# coderbot_v5_0_rev_2.net
KiCad netlist of a schematic drawn in EAGLE
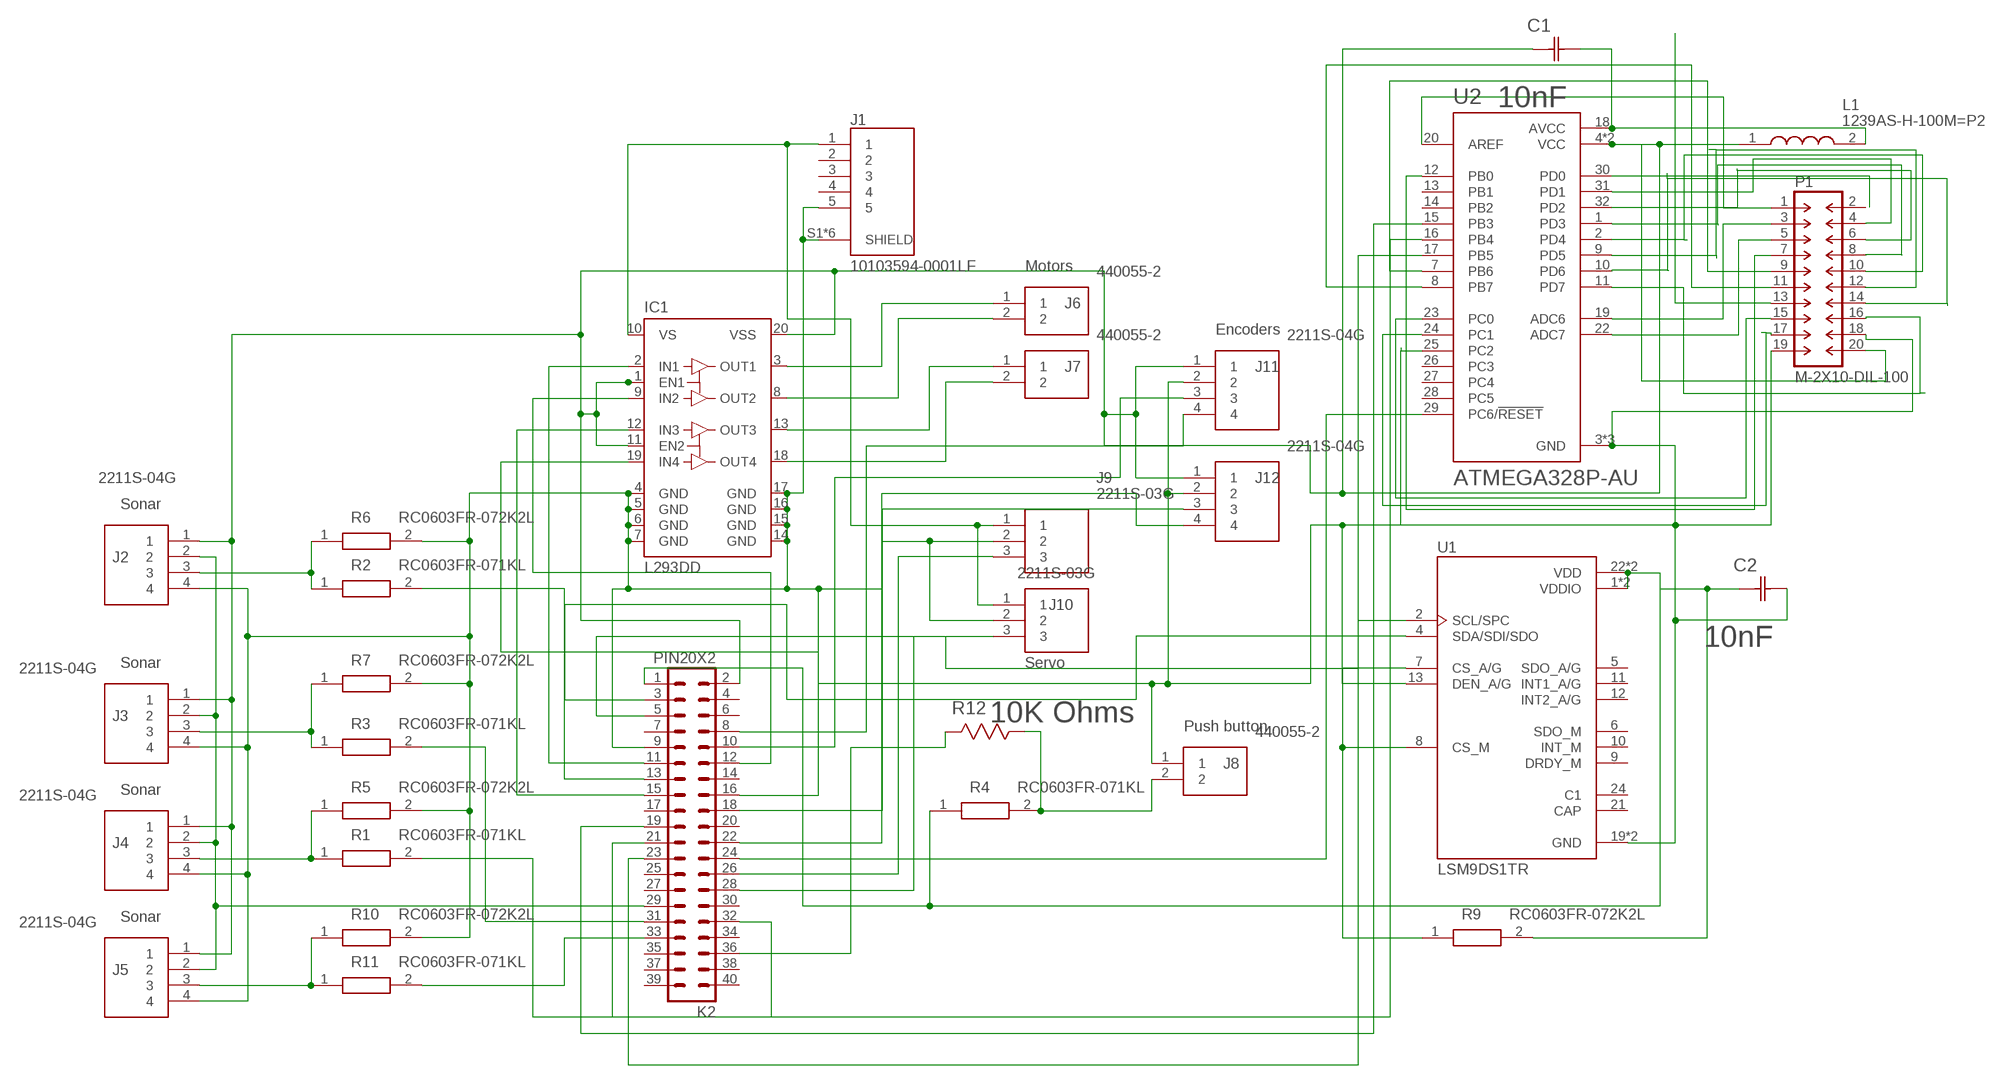
[diagram p0: schematic, sheet 1]

(export (version "E")
  (design (tool "Eeschema 10.0.6"))
  (components
    (comp (ref "C1")
      (value "10nF")
      (footprint "eagle-import:CAPC1005X55N")
      (fields (field (name "MPN") "CC0402KRX7R7BB103") (field (name "TOLERANCE") "±10%"))
      (libsource (lib "eagle-import") (part "CC0402KRX7R7BB103"))
    )
    (comp (ref "C2")
      (value "10nF")
      (footprint "eagle-import:CAPC1005X55N")
      (fields (field (name "MPN") "CC0402KRX7R7BB103") (field (name "TOLERANCE") "±10%"))
      (libsource (lib "eagle-import") (part "CC0402KRX7R7BB103"))
    )
    (comp (ref "IC1")
      (value "L293DD")
      (footprint "eagle-import:SO20")
      (libsource (lib "eagle-import") (part "L293DD"))
    )
    (comp (ref "J1")
      (value "10103594-0001LF")
      (footprint "eagle-import:FCI_10103594-0001LF")
      (fields (field (name "DIGI-KEY_PART_NUMBER") "609-4050-1-ND") (field (name "MF") "Amphenol ICC"))
      (libsource (lib "eagle-import") (part "10103594-0001LF"))
    )
    (comp (ref "J2")
      (value "2211S-04G")
      (footprint "eagle-import:HDRV4W90P0X254_1X4_1016X254X87")
      (libsource (lib "eagle-import") (part "2211S-04G"))
    )
    (comp (ref "J3")
      (value "2211S-04G")
      (footprint "eagle-import:HDRV4W90P0X254_1X4_1016X254X87")
      (libsource (lib "eagle-import") (part "2211S-04G"))
    )
    (comp (ref "J4")
      (value "2211S-04G")
      (footprint "eagle-import:HDRV4W90P0X254_1X4_1016X254X87")
      (libsource (lib "eagle-import") (part "2211S-04G"))
    )
    (comp (ref "J5")
      (value "2211S-04G")
      (footprint "eagle-import:HDRV4W90P0X254_1X4_1016X254X87")
      (libsource (lib "eagle-import") (part "2211S-04G"))
    )
    (comp (ref "J6")
      (value "440055-2")
      (footprint "eagle-import:SHDR2W70P0X200_1X2_600X770X525")
      (fields (field (name "MOUSER_PART_NUMBER") "571-440055-2"))
      (libsource (lib "eagle-import") (part "440055-2"))
    )
    (comp (ref "J7")
      (value "440055-2")
      (footprint "eagle-import:SHDR2W70P0X200_1X2_600X770X525")
      (fields (field (name "MOUSER_PART_NUMBER") "571-440055-2"))
      (libsource (lib "eagle-import") (part "440055-2"))
    )
    (comp (ref "J8")
      (value "440055-2")
      (footprint "eagle-import:SHDR2W70P0X200_1X2_600X770X525")
      (fields (field (name "MOUSER_PART_NUMBER") "571-440055-2"))
      (libsource (lib "eagle-import") (part "440055-2"))
    )
    (comp (ref "J9")
      (value "2211S-03G")
      (footprint "eagle-import:HDRV3W90P0X254_1X3_762X254X874")
      (libsource (lib "eagle-import") (part "2211S-03G"))
    )
    (comp (ref "J10")
      (value "2211S-03G")
      (footprint "eagle-import:HDRV3W90P0X254_1X3_762X254X874")
      (libsource (lib "eagle-import") (part "2211S-03G"))
    )
    (comp (ref "J11")
      (value "2211S-04G")
      (footprint "eagle-import:HDRV4W90P0X254_1X4_1016X254X87")
      (libsource (lib "eagle-import") (part "2211S-04G"))
    )
    (comp (ref "J12")
      (value "2211S-04G")
      (footprint "eagle-import:HDRV4W90P0X254_1X4_1016X254X87")
      (libsource (lib "eagle-import") (part "2211S-04G"))
    )
    (comp (ref "K2")
      (value "PIN20X2")
      (footprint "eagle-import:PIN_20X2")
      (libsource (lib "eagle-import") (part "PIN20X2"))
    )
    (comp (ref "L1")
      (value "1239AS-H-100M=P2")
      (footprint "eagle-import:INDC2520X120N")
      (fields
        (field (name "MOUSER_PART_NUMBER") "81-1239AS-H-100MP2")
        (field (name "RS_PART_NUMBER") "1453485")
      )
      (libsource (lib "eagle-import") (part "1239AS-H-100M=P2"))
    )
    (comp (ref "P1")
      (value "M-2X10-DIL-100")
      (footprint "eagle-import:DIL-100-2X10")
      (libsource (lib "eagle-import") (part "M-2X10-DIL-100"))
    )
    (comp (ref "R1")
      (value "RC0603FR-071KL")
      (footprint "eagle-import:RESC1608X55N")
      (fields
        (field (name "MOUSER_PART_NUMBER") "603-RC0603FR-071KL")
        (field (name "RS_PART_NUMBER") "5048928")
      )
      (libsource (lib "eagle-import") (part "RC0603FR-071KL"))
    )
    (comp (ref "R2")
      (value "RC0603FR-071KL")
      (footprint "eagle-import:RESC1608X55N")
      (fields
        (field (name "MOUSER_PART_NUMBER") "603-RC0603FR-071KL")
        (field (name "RS_PART_NUMBER") "5048928")
      )
      (libsource (lib "eagle-import") (part "RC0603FR-071KL"))
    )
    (comp (ref "R3")
      (value "RC0603FR-071KL")
      (footprint "eagle-import:RESC1608X55N")
      (fields
        (field (name "MOUSER_PART_NUMBER") "603-RC0603FR-071KL")
        (field (name "RS_PART_NUMBER") "5048928")
      )
      (libsource (lib "eagle-import") (part "RC0603FR-071KL"))
    )
    (comp (ref "R4")
      (value "RC0603FR-071KL")
      (footprint "eagle-import:RESC1608X55N")
      (fields
        (field (name "MOUSER_PART_NUMBER") "603-RC0603FR-071KL")
        (field (name "RS_PART_NUMBER") "5048928")
      )
      (libsource (lib "eagle-import") (part "RC0603FR-071KL"))
    )
    (comp (ref "R5")
      (value "RC0603FR-072K2L")
      (footprint "eagle-import:RESC1608X55N")
      (fields
        (field (name "MOUSER_PART_NUMBER") "603-RC0603FR-072K2L")
        (field (name "RS_PART_NUMBER") "5050319")
      )
      (libsource (lib "eagle-import") (part "RC0603FR-072K2L"))
    )
    (comp (ref "R6")
      (value "RC0603FR-072K2L")
      (footprint "eagle-import:RESC1608X55N")
      (fields
        (field (name "MOUSER_PART_NUMBER") "603-RC0603FR-072K2L")
        (field (name "RS_PART_NUMBER") "5050319")
      )
      (libsource (lib "eagle-import") (part "RC0603FR-072K2L"))
    )
    (comp (ref "R7")
      (value "RC0603FR-072K2L")
      (footprint "eagle-import:RESC1608X55N")
      (fields
        (field (name "MOUSER_PART_NUMBER") "603-RC0603FR-072K2L")
        (field (name "RS_PART_NUMBER") "5050319")
      )
      (libsource (lib "eagle-import") (part "RC0603FR-072K2L"))
    )
    (comp (ref "R9")
      (value "RC0603FR-072K2L")
      (footprint "eagle-import:RESC1608X55N")
      (fields
        (field (name "MOUSER_PART_NUMBER") "603-RC0603FR-072K2L")
        (field (name "RS_PART_NUMBER") "5050319")
      )
      (libsource (lib "eagle-import") (part "RC0603FR-072K2L"))
    )
    (comp (ref "R10")
      (value "RC0603FR-072K2L")
      (footprint "eagle-import:RESC1608X55N")
      (fields
        (field (name "MOUSER_PART_NUMBER") "603-RC0603FR-072K2L")
        (field (name "RS_PART_NUMBER") "5050319")
      )
      (libsource (lib "eagle-import") (part "RC0603FR-072K2L"))
    )
    (comp (ref "R11")
      (value "RC0603FR-071KL")
      (footprint "eagle-import:RESC1608X55N")
      (fields
        (field (name "MOUSER_PART_NUMBER") "603-RC0603FR-071KL")
        (field (name "RS_PART_NUMBER") "5048928")
      )
      (libsource (lib "eagle-import") (part "RC0603FR-071KL"))
    )
    (comp (ref "R12")
      (value "10K Ohms")
      (footprint "eagle-import:RESC1608X60N")
      (fields (field (name "MPN") "RC0603FR-0710KL") (field (name "TOLERANCE") "±1%"))
      (libsource (lib "eagle-import") (part "RC0603FR-0710KL"))
    )
    (comp (ref "U1")
      (value "LSM9DS1TR")
      (footprint "eagle-import:PQFN43P300X350X102-24N")
      (fields (field (name "MF") "STMicroelectronics"))
      (libsource (lib "eagle-import") (part "LSM9DS1TR"))
    )
    (comp (ref "U2")
      (value "ATMEGA328P-AU")
      (footprint "eagle-import:QFP80P900X900X120-32N")
      (fields (field (name "MF") "Microchip"))
      (libsource (lib "eagle-import") (part "ATMEGA328P-AU"))
    )
  )
  (nets
    (net (code "1") (name "/N$16") (class "Default")
      (node (ref "J4") (pin "3") (pinfunction "3_3") (pintype "bidirectional"))
      (node (ref "J5") (pin "3") (pinfunction "3_3") (pintype "bidirectional"))
      (node (ref "R1") (pin "1") (pinfunction "1_1") (pintype "bidirectional"))
      (node (ref "R10") (pin "1") (pinfunction "1_1") (pintype "bidirectional"))
      (node (ref "R11") (pin "1") (pinfunction "1_1") (pintype "bidirectional"))
      (node (ref "R5") (pin "1") (pinfunction "1_1") (pintype "bidirectional"))
    )
    (net (code "2") (name "Net-(C1-C1)") (class "Default")
      (node (ref "C1") (pin "1") (pinfunction "C1_1") (pintype "passive"))
      (node (ref "IC1") (pin "1") (pinfunction "EN1_1") (pintype "input"))
      (node (ref "IC1") (pin "11") (pinfunction "EN2_11") (pintype "input"))
      (node (ref "IC1") (pin "20") (pinfunction "VSS_20") (pintype "power_in"))
      (node (ref "J11") (pin "1") (pinfunction "1_1") (pintype "bidirectional"))
      (node (ref "J12") (pin "1") (pinfunction "1_1") (pintype "bidirectional"))
      (node (ref "J2") (pin "1") (pinfunction "1_1") (pintype "bidirectional"))
      (node (ref "J3") (pin "1") (pinfunction "1_1") (pintype "bidirectional"))
      (node (ref "J4") (pin "1") (pinfunction "1_1") (pintype "bidirectional"))
      (node (ref "J5") (pin "1") (pinfunction "1_1") (pintype "bidirectional"))
      (node (ref "K2") (pin "2") (pinfunction "2_2") (pintype "passive"))
      (node (ref "L1") (pin "1") (pinfunction "1_1") (pintype "bidirectional"))
      (node (ref "P1") (pin "20") (pinfunction "20_20") (pintype "passive"))
      (node (ref "U2") (pin "4") (pinfunction "VCC_4") (pintype "power_in"))
      (node (ref "U2") (pin "6") (pinfunction "VCC_6") (pintype "power_in"))
    )
    (net (code "3") (name "Net-(C1-C2)") (class "Default")
      (node (ref "C1") (pin "2") (pinfunction "C2_2") (pintype "passive"))
      (node (ref "L1") (pin "2") (pinfunction "2_2") (pintype "bidirectional"))
      (node (ref "U2") (pin "18") (pinfunction "AVCC_18") (pintype "power_in"))
    )
    (net (code "4") (name "Net-(C2-C1)") (class "Default")
      (node (ref "C2") (pin "1") (pinfunction "C1_1") (pintype "passive"))
      (node (ref "K2") (pin "1") (pinfunction "1_1") (pintype "passive"))
      (node (ref "R4") (pin "1") (pinfunction "1_1") (pintype "bidirectional"))
      (node (ref "R9") (pin "2") (pinfunction "2_2") (pintype "bidirectional"))
      (node (ref "U1") (pin "1") (pinfunction "VDDIO_1") (pintype "power_in"))
      (node (ref "U1") (pin "22") (pinfunction "VDD_22") (pintype "power_in"))
      (node (ref "U1") (pin "23") (pinfunction "VDD_23") (pintype "power_in"))
      (node (ref "U1") (pin "3") (pinfunction "VDDIO_3") (pintype "power_in"))
    )
    (net (code "5") (name "Net-(C2-C2)") (class "Default")
      (node (ref "C2") (pin "2") (pinfunction "C2_2") (pintype "passive"))
      (node (ref "IC1") (pin "14") (pinfunction "GND_14") (pintype "power_in"))
      (node (ref "IC1") (pin "15") (pinfunction "GND_15") (pintype "power_in"))
      (node (ref "IC1") (pin "16") (pinfunction "GND_16") (pintype "power_in"))
      (node (ref "IC1") (pin "17") (pinfunction "GND_17") (pintype "power_in"))
      (node (ref "IC1") (pin "4") (pinfunction "GND_4") (pintype "power_in"))
      (node (ref "IC1") (pin "5") (pinfunction "GND_5") (pintype "power_in"))
      (node (ref "IC1") (pin "6") (pinfunction "GND_6") (pintype "power_in"))
      (node (ref "IC1") (pin "7") (pinfunction "GND_7") (pintype "power_in"))
      (node (ref "J1") (pin "5") (pinfunction "5_5") (pintype "passive"))
      (node (ref "J1") (pin "S1") (pinfunction "SHIELD_S1") (pintype "passive"))
      (node (ref "J1") (pin "S2") (pinfunction "SHIELD_S2") (pintype "passive"))
      (node (ref "J1") (pin "S3") (pinfunction "SHIELD_S3") (pintype "passive"))
      (node (ref "J1") (pin "S4") (pinfunction "SHIELD_S4") (pintype "passive"))
      (node (ref "J1") (pin "S5") (pinfunction "SHIELD_S5") (pintype "passive"))
      (node (ref "J1") (pin "S6") (pinfunction "SHIELD_S6") (pintype "passive"))
      (node (ref "J10") (pin "2") (pinfunction "2_2") (pintype "bidirectional"))
      (node (ref "J11") (pin "2") (pinfunction "2_2") (pintype "bidirectional"))
      (node (ref "J12") (pin "2") (pinfunction "2_2") (pintype "bidirectional"))
      (node (ref "J2") (pin "4") (pinfunction "4_4") (pintype "bidirectional"))
      (node (ref "J3") (pin "4") (pinfunction "4_4") (pintype "bidirectional"))
      (node (ref "J4") (pin "4") (pinfunction "4_4") (pintype "bidirectional"))
      (node (ref "J5") (pin "4") (pinfunction "4_4") (pintype "bidirectional"))
      (node (ref "J8") (pin "1") (pinfunction "1_1") (pintype "bidirectional"))
      (node (ref "J9") (pin "2") (pinfunction "2_2") (pintype "bidirectional"))
      (node (ref "K2") (pin "9") (pinfunction "9_9") (pintype "passive"))
      (node (ref "P1") (pin "18") (pinfunction "18_18") (pintype "passive"))
      (node (ref "R10") (pin "2") (pinfunction "2_2") (pintype "bidirectional"))
      (node (ref "R5") (pin "2") (pinfunction "2_2") (pintype "bidirectional"))
      (node (ref "R6") (pin "2") (pinfunction "2_2") (pintype "bidirectional"))
      (node (ref "R7") (pin "2") (pinfunction "2_2") (pintype "bidirectional"))
      (node (ref "U1") (pin "13") (pinfunction "DEN_A/G_13") (pintype "input"))
      (node (ref "U1") (pin "19") (pinfunction "GND_19") (pintype "power_in"))
      (node (ref "U1") (pin "20") (pinfunction "GND_20") (pintype "power_in"))
      (node (ref "U2") (pin "21") (pinfunction "GND_21") (pintype "power_in"))
      (node (ref "U2") (pin "3") (pinfunction "GND_3") (pintype "power_in"))
      (node (ref "U2") (pin "5") (pinfunction "GND_5") (pintype "power_in"))
    )
    (net (code "6") (name "Net-(IC1-IN1)") (class "Default")
      (node (ref "IC1") (pin "2") (pinfunction "IN1_2") (pintype "input"))
      (node (ref "K2") (pin "11") (pinfunction "11_11") (pintype "passive"))
    )
    (net (code "7") (name "Net-(IC1-IN2)") (class "Default")
      (node (ref "IC1") (pin "9") (pinfunction "IN2_9") (pintype "input"))
      (node (ref "K2") (pin "12") (pinfunction "12_12") (pintype "passive"))
    )
    (net (code "8") (name "Net-(IC1-IN3)") (class "Default")
      (node (ref "IC1") (pin "12") (pinfunction "IN3_12") (pintype "input"))
      (node (ref "K2") (pin "15") (pinfunction "15_15") (pintype "passive"))
    )
    (net (code "9") (name "Net-(IC1-IN4)") (class "Default")
      (node (ref "IC1") (pin "19") (pinfunction "IN4_19") (pintype "input"))
      (node (ref "K2") (pin "16") (pinfunction "16_16") (pintype "passive"))
    )
    (net (code "10") (name "Net-(IC1-OUT1)") (class "Default")
      (node (ref "IC1") (pin "3") (pinfunction "OUT1_3") (pintype "output"))
      (node (ref "J6") (pin "1") (pinfunction "1_1") (pintype "bidirectional"))
    )
    (net (code "11") (name "Net-(IC1-OUT2)") (class "Default")
      (node (ref "IC1") (pin "8") (pinfunction "OUT2_8") (pintype "output"))
      (node (ref "J6") (pin "2") (pinfunction "2_2") (pintype "bidirectional"))
    )
    (net (code "12") (name "Net-(IC1-OUT3)") (class "Default")
      (node (ref "IC1") (pin "13") (pinfunction "OUT3_13") (pintype "output"))
      (node (ref "J7") (pin "1") (pinfunction "1_1") (pintype "bidirectional"))
    )
    (net (code "13") (name "Net-(IC1-OUT4)") (class "Default")
      (node (ref "IC1") (pin "18") (pinfunction "OUT4_18") (pintype "output"))
      (node (ref "J7") (pin "2") (pinfunction "2_2") (pintype "bidirectional"))
    )
    (net (code "14") (name "Net-(IC1-VS)") (class "Default")
      (node (ref "IC1") (pin "10") (pinfunction "VS_10") (pintype "power_in"))
      (node (ref "J1") (pin "1") (pinfunction "1_1") (pintype "passive"))
      (node (ref "J10") (pin "1") (pinfunction "1_1") (pintype "bidirectional"))
      (node (ref "J9") (pin "1") (pinfunction "1_1") (pintype "bidirectional"))
    )
    (net (code "15") (name "Net-(J2-Pad2)") (class "Default")
      (node (ref "J2") (pin "2") (pinfunction "2_2") (pintype "bidirectional"))
      (node (ref "J3") (pin "2") (pinfunction "2_2") (pintype "bidirectional"))
      (node (ref "J4") (pin "2") (pinfunction "2_2") (pintype "bidirectional"))
      (node (ref "J5") (pin "2") (pinfunction "2_2") (pintype "bidirectional"))
      (node (ref "K2") (pin "29") (pinfunction "29_29") (pintype "passive"))
    )
    (net (code "16") (name "Net-(J2-Pad3)") (class "Default")
      (node (ref "J2") (pin "3") (pinfunction "3_3") (pintype "bidirectional"))
      (node (ref "R2") (pin "1") (pinfunction "1_1") (pintype "bidirectional"))
      (node (ref "R6") (pin "1") (pinfunction "1_1") (pintype "bidirectional"))
    )
    (net (code "17") (name "Net-(J3-Pad3)") (class "Default")
      (node (ref "J3") (pin "3") (pinfunction "3_3") (pintype "bidirectional"))
      (node (ref "R3") (pin "1") (pinfunction "1_1") (pintype "bidirectional"))
      (node (ref "R7") (pin "1") (pinfunction "1_1") (pintype "bidirectional"))
    )
    (net (code "18") (name "Net-(J9-Pad3)") (class "Default")
      (node (ref "J9") (pin "3") (pinfunction "3_3") (pintype "bidirectional"))
      (node (ref "K2") (pin "26") (pinfunction "26_26") (pintype "passive"))
    )
    (net (code "19") (name "Net-(J10-Pad3)") (class "Default")
      (node (ref "J10") (pin "3") (pinfunction "3_3") (pintype "bidirectional"))
      (node (ref "K2") (pin "28") (pinfunction "28_28") (pintype "passive"))
    )
    (net (code "20") (name "Net-(J11-Pad3)") (class "Default")
      (node (ref "J11") (pin "3") (pinfunction "3_3") (pintype "bidirectional"))
      (node (ref "K2") (pin "10") (pinfunction "10_10") (pintype "passive"))
    )
    (net (code "21") (name "Net-(J11-Pad4)") (class "Default")
      (node (ref "J11") (pin "4") (pinfunction "4_4") (pintype "bidirectional"))
      (node (ref "K2") (pin "8") (pinfunction "8_8") (pintype "passive"))
    )
    (net (code "22") (name "Net-(J12-Pad3)") (class "Default")
      (node (ref "J12") (pin "3") (pinfunction "3_3") (pintype "bidirectional"))
      (node (ref "K2") (pin "18") (pinfunction "18_18") (pintype "passive"))
    )
    (net (code "23") (name "Net-(J12-Pad4)") (class "Default")
      (node (ref "J12") (pin "4") (pinfunction "4_4") (pintype "bidirectional"))
      (node (ref "K2") (pin "22") (pinfunction "22_22") (pintype "passive"))
    )
    (net (code "24") (name "Net-(K2-Pad13)") (class "Default")
      (node (ref "K2") (pin "13") (pinfunction "13_13") (pintype "passive"))
      (node (ref "R2") (pin "2") (pinfunction "2_2") (pintype "bidirectional"))
    )
    (net (code "25") (name "Net-(K2-Pad31)") (class "Default")
      (node (ref "K2") (pin "31") (pinfunction "31_31") (pintype "passive"))
      (node (ref "R3") (pin "2") (pinfunction "2_2") (pintype "bidirectional"))
    )
    (net (code "26") (name "Net-(K2-Pad32)") (class "Default")
      (node (ref "K2") (pin "32") (pinfunction "32_32") (pintype "passive"))
      (node (ref "R1") (pin "2") (pinfunction "2_2") (pintype "bidirectional"))
    )
    (net (code "27") (name "Net-(K2-Pad33)") (class "Default")
      (node (ref "K2") (pin "33") (pinfunction "33_33") (pintype "passive"))
      (node (ref "R11") (pin "2") (pinfunction "2_2") (pintype "bidirectional"))
    )
    (net (code "28") (name "Net-(R12-R1)") (class "Default")
      (node (ref "J8") (pin "2") (pinfunction "2_2") (pintype "bidirectional"))
      (node (ref "R12") (pin "1") (pinfunction "R1_1") (pintype "passive"))
      (node (ref "R4") (pin "2") (pinfunction "2_2") (pintype "bidirectional"))
    )
    (net (code "29") (name "Net-(R12-R2)") (class "Default")
      (node (ref "K2") (pin "36") (pinfunction "36_36") (pintype "passive"))
      (node (ref "R12") (pin "2") (pinfunction "R2_2") (pintype "passive"))
    )
    (net (code "30") (name "Net-(U1-CS_A{slash}G)") (class "Default")
      (node (ref "R9") (pin "1") (pinfunction "1_1") (pintype "bidirectional"))
      (node (ref "U1") (pin "7") (pinfunction "CS_A/G_7") (pintype "input"))
      (node (ref "U1") (pin "8") (pinfunction "CS_M_8") (pintype "input"))
    )
    (net (code "31") (name "Net-(U1-SCL{slash}SPC)") (class "Default")
      (node (ref "K2") (pin "5") (pinfunction "5_5") (pintype "passive"))
      (node (ref "U1") (pin "2") (pinfunction "SCL/SPC_2") (pintype "input"))
    )
    (net (code "32") (name "Net-(U1-SDA{slash}SDI{slash}SDO)") (class "Default")
      (node (ref "K2") (pin "3") (pinfunction "3_3") (pintype "passive"))
      (node (ref "U1") (pin "4") (pinfunction "SDA/SDI/SDO_4") (pintype "bidirectional"))
    )
    (net (code "33") (name "Net-(U2-ADC6)") (class "Default")
      (node (ref "P1") (pin "3") (pinfunction "3_3") (pintype "passive"))
      (node (ref "U2") (pin "19") (pinfunction "ADC6_19") (pintype "bidirectional"))
    )
    (net (code "34") (name "Net-(U2-ADC7)") (class "Default")
      (node (ref "P1") (pin "5") (pinfunction "5_5") (pintype "passive"))
      (node (ref "U2") (pin "22") (pinfunction "ADC7_22") (pintype "bidirectional"))
    )
    (net (code "35") (name "Net-(U2-AREF)") (class "Default")
      (node (ref "P1") (pin "1") (pinfunction "1_1") (pintype "passive"))
      (node (ref "U2") (pin "20") (pinfunction "AREF_20") (pintype "input"))
    )
    (net (code "36") (name "Net-(U2-PB0)") (class "Default")
      (node (ref "P1") (pin "7") (pinfunction "7_7") (pintype "passive"))
      (node (ref "U2") (pin "12") (pinfunction "PB0_12") (pintype "bidirectional"))
    )
    (net (code "37") (name "Net-(U2-PB3)") (class "Default")
      (node (ref "K2") (pin "19") (pinfunction "19_19") (pintype "passive"))
      (node (ref "U2") (pin "15") (pinfunction "PB3_15") (pintype "bidirectional"))
    )
    (net (code "38") (name "Net-(U2-PB4)") (class "Default")
      (node (ref "K2") (pin "21") (pinfunction "21_21") (pintype "passive"))
      (node (ref "U2") (pin "16") (pinfunction "PB4_16") (pintype "bidirectional"))
    )
    (net (code "39") (name "Net-(U2-PB5)") (class "Default")
      (node (ref "K2") (pin "23") (pinfunction "23_23") (pintype "passive"))
      (node (ref "U2") (pin "17") (pinfunction "PB5_17") (pintype "bidirectional"))
    )
    (net (code "40") (name "Net-(U2-PB6)") (class "Default")
      (node (ref "P1") (pin "9") (pinfunction "9_9") (pintype "passive"))
      (node (ref "U2") (pin "7") (pinfunction "PB6_7") (pintype "bidirectional"))
    )
    (net (code "41") (name "Net-(U2-PB7)") (class "Default")
      (node (ref "P1") (pin "11") (pinfunction "11_11") (pintype "passive"))
      (node (ref "U2") (pin "8") (pinfunction "PB7_8") (pintype "bidirectional"))
    )
    (net (code "42") (name "Net-(U2-PC0)") (class "Default")
      (node (ref "P1") (pin "15") (pinfunction "15_15") (pintype "passive"))
      (node (ref "U2") (pin "23") (pinfunction "PC0_23") (pintype "bidirectional"))
    )
    (net (code "43") (name "Net-(U2-PC1)") (class "Default")
      (node (ref "P1") (pin "17") (pinfunction "17_17") (pintype "passive"))
      (node (ref "U2") (pin "24") (pinfunction "PC1_24") (pintype "bidirectional"))
    )
    (net (code "44") (name "Net-(U2-PC2)") (class "Default")
      (node (ref "P1") (pin "19") (pinfunction "19_19") (pintype "passive"))
      (node (ref "U2") (pin "25") (pinfunction "PC2_25") (pintype "bidirectional"))
    )
    (net (code "45") (name "Net-(U2-PC6{slash}~{RESET})") (class "Default")
      (node (ref "K2") (pin "24") (pinfunction "24_24") (pintype "passive"))
      (node (ref "U2") (pin "29") (pinfunction "PC6/~{RESET}_29") (pintype "bidirectional"))
    )
    (net (code "46") (name "Net-(U2-PD1)") (class "Default")
      (node (ref "P1") (pin "4") (pinfunction "4_4") (pintype "passive"))
      (node (ref "U2") (pin "31") (pinfunction "PD1_31") (pintype "bidirectional"))
    )
    (net (code "47") (name "Net-(U2-PD2)") (class "Default")
      (node (ref "P1") (pin "6") (pinfunction "6_6") (pintype "passive"))
      (node (ref "U2") (pin "32") (pinfunction "PD2_32") (pintype "bidirectional"))
    )
    (net (code "48") (name "Net-(U2-PD3)") (class "Default")
      (node (ref "P1") (pin "8") (pinfunction "8_8") (pintype "passive"))
      (node (ref "U2") (pin "1") (pinfunction "PD3_1") (pintype "bidirectional"))
    )
    (net (code "49") (name "Net-(U2-PD4)") (class "Default")
      (node (ref "P1") (pin "10") (pinfunction "10_10") (pintype "passive"))
      (node (ref "U2") (pin "2") (pinfunction "PD4_2") (pintype "bidirectional"))
    )
    (net (code "50") (name "Net-(U2-PD5)") (class "Default")
      (node (ref "P1") (pin "12") (pinfunction "12_12") (pintype "passive"))
      (node (ref "U2") (pin "9") (pinfunction "PD5_9") (pintype "bidirectional"))
    )
    (net (code "51") (name "Net-(U2-PD6)") (class "Default")
      (node (ref "P1") (pin "14") (pinfunction "14_14") (pintype "passive"))
      (node (ref "U2") (pin "10") (pinfunction "PD6_10") (pintype "bidirectional"))
    )
    (net (code "52") (name "Net-(U2-PD7)") (class "Default")
      (node (ref "P1") (pin "16") (pinfunction "16_16") (pintype "passive"))
      (node (ref "U2") (pin "11") (pinfunction "PD7_11") (pintype "bidirectional"))
    )
    (net (code "53") (name "unconnected-(J1-Pad2)") (class "Default")
      (node (ref "J1") (pin "2") (pinfunction "2_2") (pintype "passive"))
    )
    (net (code "54") (name "unconnected-(J1-Pad3)") (class "Default")
      (node (ref "J1") (pin "3") (pinfunction "3_3") (pintype "passive"))
    )
    (net (code "55") (name "unconnected-(J1-Pad4)") (class "Default")
      (node (ref "J1") (pin "4") (pinfunction "4_4") (pintype "passive"))
    )
    (net (code "56") (name "unconnected-(K2-Pad4)") (class "Default")
      (node (ref "K2") (pin "4") (pinfunction "4_4") (pintype "passive"))
    )
    (net (code "57") (name "unconnected-(K2-Pad6)") (class "Default")
      (node (ref "K2") (pin "6") (pinfunction "6_6") (pintype "passive"))
    )
    (net (code "58") (name "unconnected-(K2-Pad7)") (class "Default")
      (node (ref "K2") (pin "7") (pinfunction "7_7") (pintype "passive"))
    )
    (net (code "59") (name "unconnected-(K2-Pad14)") (class "Default")
      (node (ref "K2") (pin "14") (pinfunction "14_14") (pintype "passive"))
    )
    (net (code "60") (name "unconnected-(K2-Pad17)") (class "Default")
      (node (ref "K2") (pin "17") (pinfunction "17_17") (pintype "passive"))
    )
    (net (code "61") (name "unconnected-(K2-Pad20)") (class "Default")
      (node (ref "K2") (pin "20") (pinfunction "20_20") (pintype "passive"))
    )
    (net (code "62") (name "unconnected-(K2-Pad25)") (class "Default")
      (node (ref "K2") (pin "25") (pinfunction "25_25") (pintype "passive"))
    )
    (net (code "63") (name "unconnected-(K2-Pad27)") (class "Default")
      (node (ref "K2") (pin "27") (pinfunction "27_27") (pintype "passive"))
    )
    (net (code "64") (name "unconnected-(K2-Pad30)") (class "Default")
      (node (ref "K2") (pin "30") (pinfunction "30_30") (pintype "passive"))
    )
    (net (code "65") (name "unconnected-(K2-Pad34)") (class "Default")
      (node (ref "K2") (pin "34") (pinfunction "34_34") (pintype "passive"))
    )
    (net (code "66") (name "unconnected-(K2-Pad35)") (class "Default")
      (node (ref "K2") (pin "35") (pinfunction "35_35") (pintype "passive"))
    )
    (net (code "67") (name "unconnected-(K2-Pad37)") (class "Default")
      (node (ref "K2") (pin "37") (pinfunction "37_37") (pintype "passive"))
    )
    (net (code "68") (name "unconnected-(K2-Pad38)") (class "Default")
      (node (ref "K2") (pin "38") (pinfunction "38_38") (pintype "passive"))
    )
    (net (code "69") (name "unconnected-(K2-Pad39)") (class "Default")
      (node (ref "K2") (pin "39") (pinfunction "39_39") (pintype "passive"))
    )
    (net (code "70") (name "unconnected-(K2-Pad40)") (class "Default")
      (node (ref "K2") (pin "40") (pinfunction "40_40") (pintype "passive"))
    )
    (net (code "71") (name "unconnected-(P1-Pad2)") (class "Default")
      (node (ref "P1") (pin "2") (pinfunction "2_2") (pintype "passive"))
    )
    (net (code "72") (name "unconnected-(P1-Pad13)") (class "Default")
      (node (ref "P1") (pin "13") (pinfunction "13_13") (pintype "passive"))
    )
    (net (code "73") (name "unconnected-(U1-C1-Pad24)") (class "Default")
      (node (ref "U1") (pin "24") (pinfunction "C1_24") (pintype "passive"))
    )
    (net (code "74") (name "unconnected-(U1-CAP-Pad21)") (class "Default")
      (node (ref "U1") (pin "21") (pinfunction "CAP_21") (pintype "passive"))
    )
    (net (code "75") (name "unconnected-(U1-DRDY_M-Pad9)") (class "Default")
      (node (ref "U1") (pin "9") (pinfunction "DRDY_M_9") (pintype "output"))
    )
    (net (code "76") (name "unconnected-(U1-INT1_A{slash}G-Pad11)") (class "Default")
      (node (ref "U1") (pin "11") (pinfunction "INT1_A/G_11") (pintype "output"))
    )
    (net (code "77") (name "unconnected-(U1-INT2_A{slash}G-Pad12)") (class "Default")
      (node (ref "U1") (pin "12") (pinfunction "INT2_A/G_12") (pintype "output"))
    )
    (net (code "78") (name "unconnected-(U1-INT_M-Pad10)") (class "Default")
      (node (ref "U1") (pin "10") (pinfunction "INT_M_10") (pintype "output"))
    )
    (net (code "79") (name "unconnected-(U1-SDO_A{slash}G-Pad5)") (class "Default")
      (node (ref "U1") (pin "5") (pinfunction "SDO_A/G_5") (pintype "output"))
    )
    (net (code "80") (name "unconnected-(U1-SDO_M-Pad6)") (class "Default")
      (node (ref "U1") (pin "6") (pinfunction "SDO_M_6") (pintype "output"))
    )
    (net (code "81") (name "unconnected-(U2-PB1-Pad13)") (class "Default")
      (node (ref "U2") (pin "13") (pinfunction "PB1_13") (pintype "bidirectional"))
    )
    (net (code "82") (name "unconnected-(U2-PB2-Pad14)") (class "Default")
      (node (ref "U2") (pin "14") (pinfunction "PB2_14") (pintype "bidirectional"))
    )
    (net (code "83") (name "unconnected-(U2-PC3-Pad26)") (class "Default")
      (node (ref "U2") (pin "26") (pinfunction "PC3_26") (pintype "bidirectional"))
    )
    (net (code "84") (name "unconnected-(U2-PC4-Pad27)") (class "Default")
      (node (ref "U2") (pin "27") (pinfunction "PC4_27") (pintype "bidirectional"))
    )
    (net (code "85") (name "unconnected-(U2-PC5-Pad28)") (class "Default")
      (node (ref "U2") (pin "28") (pinfunction "PC5_28") (pintype "bidirectional"))
    )
    (net (code "86") (name "unconnected-(U2-PD0-Pad30)") (class "Default")
      (node (ref "U2") (pin "30") (pinfunction "PD0_30") (pintype "bidirectional"))
    )
  )
)
